# circuit.net
KiCad netlist of a schematic drawn in EAGLE
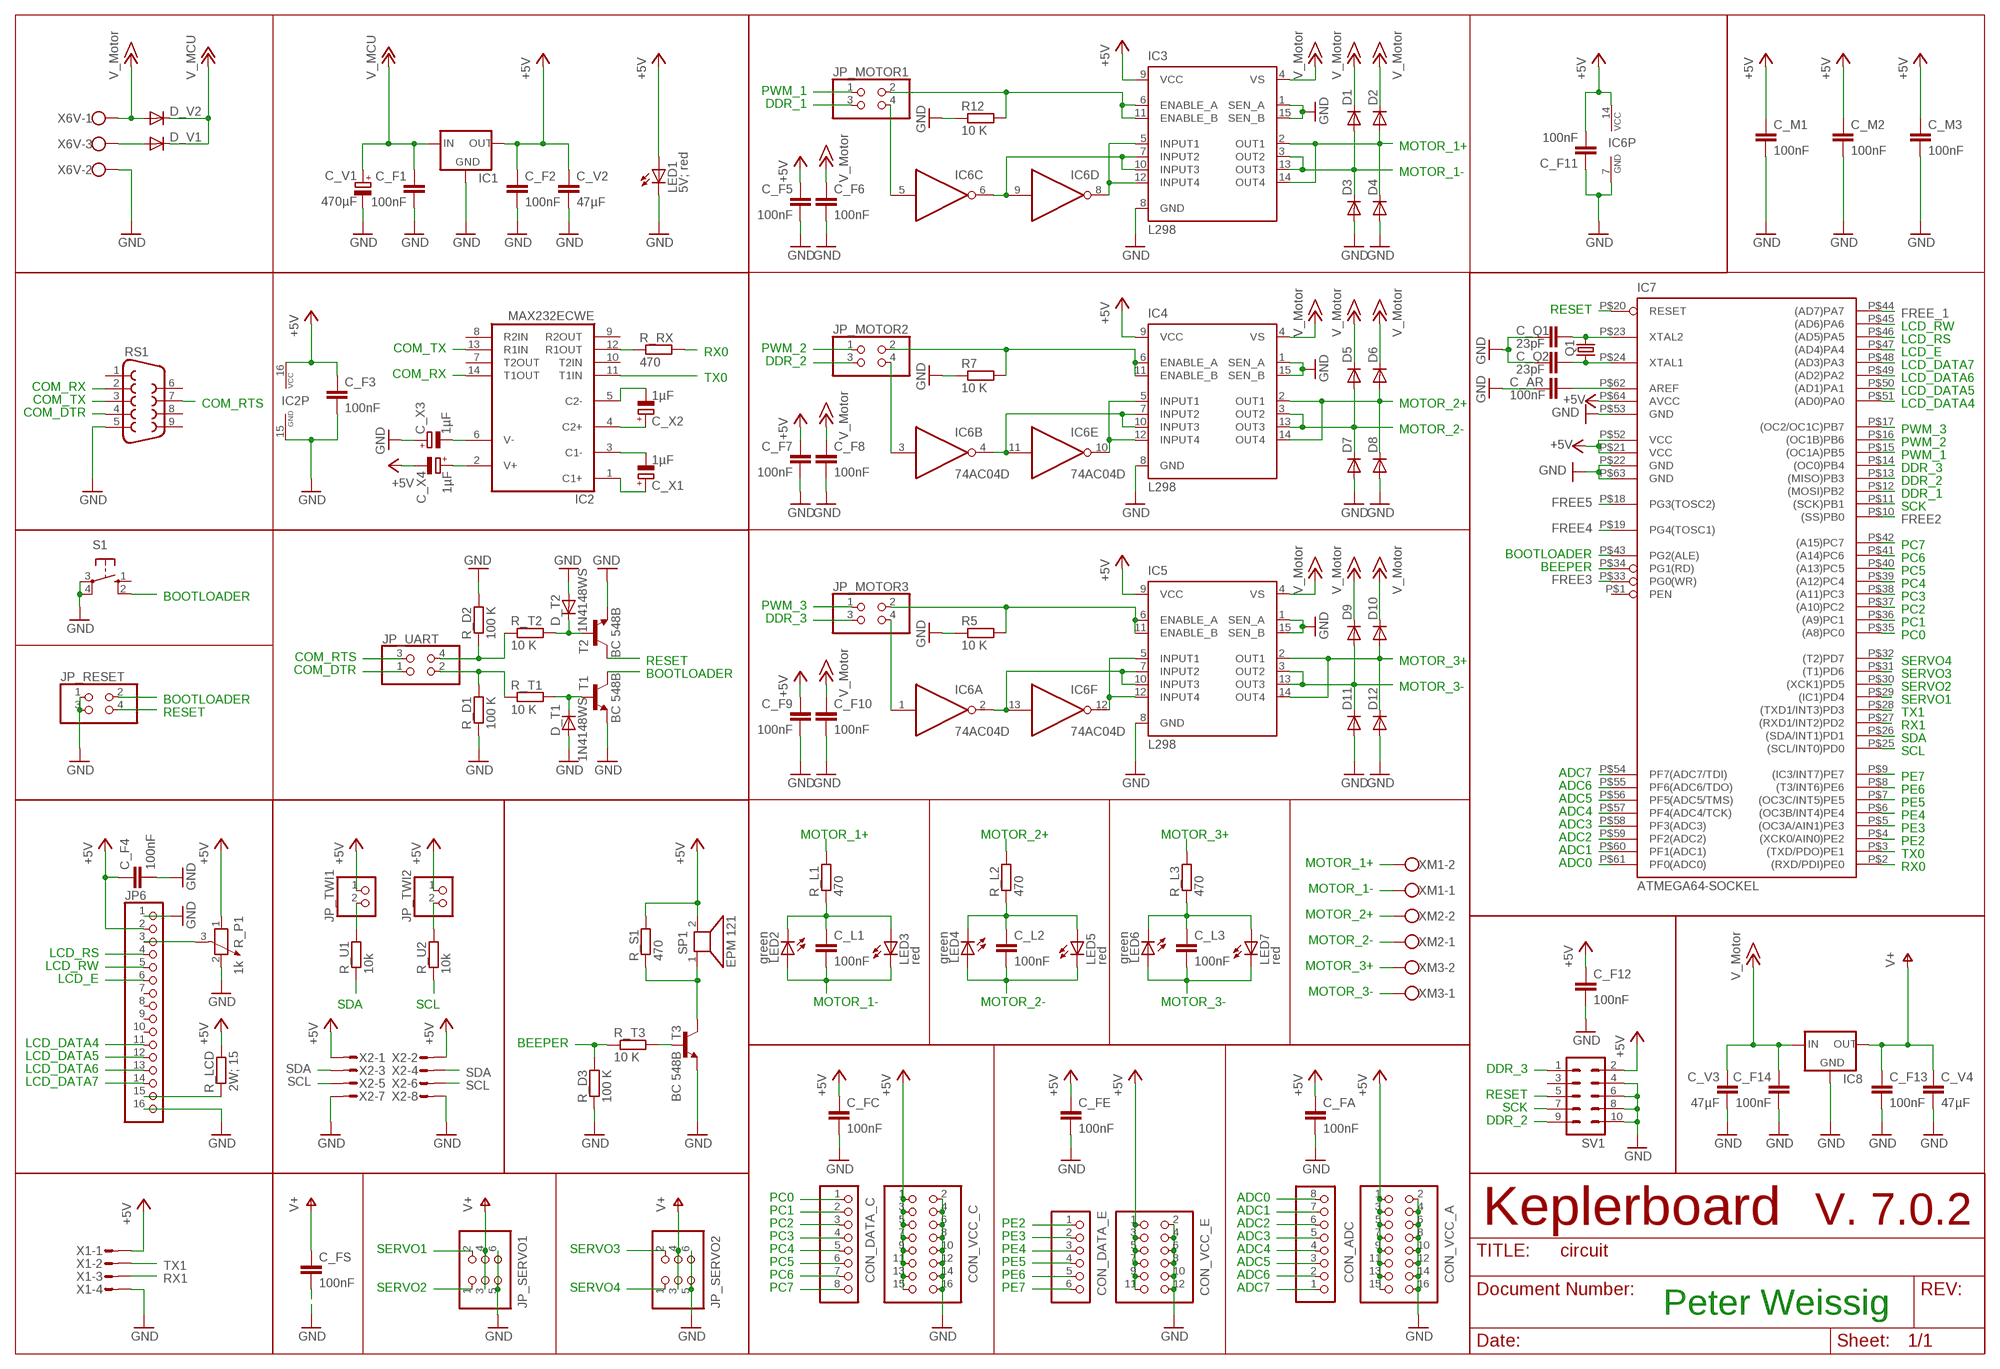
[diagram p0: schematic, sheet 1]

(export (version "E")
  (design (tool "Eeschema 10.0.6"))
  (components
    (comp (ref "CON_ADC")
      (value "PINHD-1X8")
      (footprint "eagle-import:1X08")
      (libsource (lib "eagle-import") (part "PINHD-1X8"))
    )
    (comp (ref "CON_DATA_C")
      (value "PINHD-1X8")
      (footprint "eagle-import:1X08")
      (libsource (lib "eagle-import") (part "PINHD-1X8"))
    )
    (comp (ref "CON_DATA_E")
      (value "PINHD-1X6")
      (footprint "eagle-import:1X06")
      (libsource (lib "eagle-import") (part "PINHD-1X6"))
    )
    (comp (ref "CON_VCC_A")
      (value "PINHD-2X8")
      (footprint "eagle-import:2X08")
      (libsource (lib "eagle-import") (part "PINHD-2X8"))
    )
    (comp (ref "CON_VCC_C")
      (value "PINHD-2X8")
      (footprint "eagle-import:2X08")
      (libsource (lib "eagle-import") (part "PINHD-2X8"))
    )
    (comp (ref "CON_VCC_E")
      (value "PINHD-2X6")
      (footprint "eagle-import:2X06")
      (libsource (lib "eagle-import") (part "PINHD-2X6"))
    )
    (comp (ref "C_AR")
      (value "100nF")
      (footprint "eagle-import:C025-025X050")
      (libsource (lib "eagle-import") (part "C-EU025-025X050"))
    )
    (comp (ref "C_F1")
      (value "100nF")
      (footprint "eagle-import:C1206K")
      (libsource (lib "eagle-import") (part "C-EUC1206K"))
    )
    (comp (ref "C_F2")
      (value "100nF")
      (footprint "eagle-import:C1206K")
      (libsource (lib "eagle-import") (part "C-EUC1206K"))
    )
    (comp (ref "C_F3")
      (value "100nF")
      (footprint "eagle-import:C1206K")
      (libsource (lib "eagle-import") (part "C-EUC1206K"))
    )
    (comp (ref "C_F4")
      (value "100nF")
      (footprint "eagle-import:C025-025X050")
      (libsource (lib "eagle-import") (part "C-EU025-025X050"))
    )
    (comp (ref "C_F5")
      (value "100nF")
      (footprint "eagle-import:C1206K")
      (libsource (lib "eagle-import") (part "C-EUC1206K"))
    )
    (comp (ref "C_F6")
      (value "100nF")
      (footprint "eagle-import:C1206K")
      (libsource (lib "eagle-import") (part "C-EUC1206K"))
    )
    (comp (ref "C_F7")
      (value "100nF")
      (footprint "eagle-import:C1206K")
      (libsource (lib "eagle-import") (part "C-EUC1206K"))
    )
    (comp (ref "C_F8")
      (value "100nF")
      (footprint "eagle-import:C1206K")
      (libsource (lib "eagle-import") (part "C-EUC1206K"))
    )
    (comp (ref "C_F9")
      (value "100nF")
      (footprint "eagle-import:C1206K")
      (libsource (lib "eagle-import") (part "C-EUC1206K"))
    )
    (comp (ref "C_F10")
      (value "100nF")
      (footprint "eagle-import:C1206K")
      (libsource (lib "eagle-import") (part "C-EUC1206K"))
    )
    (comp (ref "C_F11")
      (value "100nF")
      (footprint "eagle-import:C1206K")
      (libsource (lib "eagle-import") (part "C-EUC1206K"))
    )
    (comp (ref "C_F12")
      (value "100nF")
      (footprint "eagle-import:C1206K")
      (libsource (lib "eagle-import") (part "C-EUC1206K"))
    )
    (comp (ref "C_F13")
      (value "100nF")
      (footprint "eagle-import:C1206K")
      (libsource (lib "eagle-import") (part "C-EUC1206K"))
    )
    (comp (ref "C_F14")
      (value "100nF")
      (footprint "eagle-import:C1206K")
      (libsource (lib "eagle-import") (part "C-EUC1206K"))
    )
    (comp (ref "C_FA")
      (value "100nF")
      (footprint "eagle-import:C025-025X050")
      (libsource (lib "eagle-import") (part "C-EU025-025X050"))
    )
    (comp (ref "C_FC")
      (value "100nF")
      (footprint "eagle-import:C025-025X050")
      (libsource (lib "eagle-import") (part "C-EU025-025X050"))
    )
    (comp (ref "C_FE")
      (value "100nF")
      (footprint "eagle-import:C025-025X050")
      (libsource (lib "eagle-import") (part "C-EU025-025X050"))
    )
    (comp (ref "C_FS")
      (value "100nF")
      (footprint "eagle-import:C1206K")
      (libsource (lib "eagle-import") (part "C-EUC1206K"))
    )
    (comp (ref "C_L1")
      (value "100nF")
      (footprint "eagle-import:C1206K")
      (libsource (lib "eagle-import") (part "C-EUC1206K"))
    )
    (comp (ref "C_L2")
      (value "100nF")
      (footprint "eagle-import:C1206K")
      (libsource (lib "eagle-import") (part "C-EUC1206K"))
    )
    (comp (ref "C_L3")
      (value "100nF")
      (footprint "eagle-import:C1206K")
      (libsource (lib "eagle-import") (part "C-EUC1206K"))
    )
    (comp (ref "C_M1")
      (value "100nF")
      (footprint "eagle-import:C025-025X050")
      (libsource (lib "eagle-import") (part "C-EU025-025X050"))
    )
    (comp (ref "C_M2")
      (value "100nF")
      (footprint "eagle-import:C025-025X050")
      (libsource (lib "eagle-import") (part "C-EU025-025X050"))
    )
    (comp (ref "C_M3")
      (value "100nF")
      (footprint "eagle-import:C025-025X050")
      (libsource (lib "eagle-import") (part "C-EU025-025X050"))
    )
    (comp (ref "C_Q1")
      (value "23pF")
      (footprint "eagle-import:C3216")
      (libsource (lib "eagle-import") (part "C-EUC3216"))
    )
    (comp (ref "C_Q2")
      (value "23pF")
      (footprint "eagle-import:C3216")
      (libsource (lib "eagle-import") (part "C-EUC3216"))
    )
    (comp (ref "C_V1")
      (value "470µF")
      (footprint "eagle-import:E5-10,5")
      (libsource (lib "eagle-import") (part "CPOL-EUE5-10.5"))
    )
    (comp (ref "C_V2")
      (value "47µF")
      (footprint "eagle-import:C1210K")
      (libsource (lib "eagle-import") (part "C-EUC1210K"))
    )
    (comp (ref "C_V3")
      (value "47µF")
      (footprint "eagle-import:C1210K")
      (libsource (lib "eagle-import") (part "C-EUC1210K"))
    )
    (comp (ref "C_V4")
      (value "47µF")
      (footprint "eagle-import:C1210K")
      (libsource (lib "eagle-import") (part "C-EUC1210K"))
    )
    (comp (ref "C_X1")
      (value "1µF")
      (footprint "eagle-import:A_3216-18W")
      (libsource (lib "eagle-import") (part "CPOL-EUA/3216-18W"))
    )
    (comp (ref "C_X2")
      (value "1µF")
      (footprint "eagle-import:A_3216-18W")
      (libsource (lib "eagle-import") (part "CPOL-EUA/3216-18W"))
    )
    (comp (ref "C_X3")
      (value "1µF")
      (footprint "eagle-import:A_3216-18W")
      (libsource (lib "eagle-import") (part "CPOL-EUA/3216-18W"))
    )
    (comp (ref "C_X4")
      (value "1µF")
      (footprint "eagle-import:A_3216-18W")
      (libsource (lib "eagle-import") (part "CPOL-EUA/3216-18W"))
    )
    (comp (ref "D1")
      (value "DIODE-SMC")
      (footprint "eagle-import:SMC")
      (libsource (lib "eagle-import") (part "DIODE-SMC"))
    )
    (comp (ref "D2")
      (value "DIODE-SMC")
      (footprint "eagle-import:SMC")
      (libsource (lib "eagle-import") (part "DIODE-SMC"))
    )
    (comp (ref "D3")
      (value "DIODE-SMC")
      (footprint "eagle-import:SMC")
      (libsource (lib "eagle-import") (part "DIODE-SMC"))
    )
    (comp (ref "D4")
      (value "DIODE-SMC")
      (footprint "eagle-import:SMC")
      (libsource (lib "eagle-import") (part "DIODE-SMC"))
    )
    (comp (ref "D5")
      (value "DIODE-SMC")
      (footprint "eagle-import:SMC")
      (libsource (lib "eagle-import") (part "DIODE-SMC"))
    )
    (comp (ref "D6")
      (value "DIODE-SMC")
      (footprint "eagle-import:SMC")
      (libsource (lib "eagle-import") (part "DIODE-SMC"))
    )
    (comp (ref "D7")
      (value "DIODE-SMC")
      (footprint "eagle-import:SMC")
      (libsource (lib "eagle-import") (part "DIODE-SMC"))
    )
    (comp (ref "D8")
      (value "DIODE-SMC")
      (footprint "eagle-import:SMC")
      (libsource (lib "eagle-import") (part "DIODE-SMC"))
    )
    (comp (ref "D9")
      (value "DIODE-SMC")
      (footprint "eagle-import:SMC")
      (libsource (lib "eagle-import") (part "DIODE-SMC"))
    )
    (comp (ref "D10")
      (value "DIODE-SMC")
      (footprint "eagle-import:SMC")
      (libsource (lib "eagle-import") (part "DIODE-SMC"))
    )
    (comp (ref "D11")
      (value "DIODE-SMC")
      (footprint "eagle-import:SMC")
      (libsource (lib "eagle-import") (part "DIODE-SMC"))
    )
    (comp (ref "D12")
      (value "DIODE-SMC")
      (footprint "eagle-import:SMC")
      (libsource (lib "eagle-import") (part "DIODE-SMC"))
    )
    (comp (ref "D_T1")
      (value "1N4148WS")
      (footprint "eagle-import:SOD323-W")
      (libsource (lib "eagle-import") (part "DIODE-SOD323-W"))
    )
    (comp (ref "D_T2")
      (value "1N4148WS")
      (footprint "eagle-import:SOD323-W")
      (libsource (lib "eagle-import") (part "DIODE-SOD323-W"))
    )
    (comp (ref "D_V1")
      (value "DIODE-SMC")
      (footprint "eagle-import:SMC")
      (libsource (lib "eagle-import") (part "DIODE-SMC"))
    )
    (comp (ref "D_V2")
      (value "DIODE-SMC")
      (footprint "eagle-import:SMC")
      (libsource (lib "eagle-import") (part "DIODE-SMC"))
    )
    (comp (ref "IC1")
      (value "78XXS")
      (footprint "eagle-import:78XXS")
      (libsource (lib "eagle-import") (part "78XXS"))
    )
    (comp (ref "IC2")
      (value "MAX232ECWE")
      (footprint "eagle-import:SO16L")
      (libsource (lib "eagle-import") (part "MAX232ECWE"))
    )
    (comp (ref "IC3")
      (value "L298")
      (footprint "eagle-import:MULTIWATT-15")
      (fields (field (name "MPN") "L298N"))
      (libsource (lib "eagle-import") (part "L298"))
    )
    (comp (ref "IC4")
      (value "L298")
      (footprint "eagle-import:MULTIWATT-15")
      (fields (field (name "MPN") "L298N"))
      (libsource (lib "eagle-import") (part "L298"))
    )
    (comp (ref "IC5")
      (value "L298")
      (footprint "eagle-import:MULTIWATT-15")
      (fields (field (name "MPN") "L298N"))
      (libsource (lib "eagle-import") (part "L298"))
    )
    (comp (ref "IC6")
      (value "74AC04D")
      (footprint "eagle-import:SO14")
      (libsource (lib "eagle-import") (part "7404DAC"))
    )
    (comp (ref "IC7")
      (value "ATMEGA64-SOCKEL")
      (footprint "eagle-import:SOCKEL_TQFP64")
      (libsource (lib "eagle-import") (part "ATMEGA64-SOCKEL"))
    )
    (comp (ref "IC8")
      (value "78XXS")
      (footprint "eagle-import:78XXS")
      (libsource (lib "eagle-import") (part "78XXS"))
    )
    (comp (ref "JP6")
      (value "PINHD-1X16")
      (footprint "eagle-import:1X16")
      (libsource (lib "eagle-import") (part "PINHD-1X16"))
    )
    (comp (ref "JP_MOTOR1")
      (value "PINHD-2X2")
      (footprint "eagle-import:2X02")
      (libsource (lib "eagle-import") (part "PINHD-2X2"))
    )
    (comp (ref "JP_MOTOR2")
      (value "PINHD-2X2")
      (footprint "eagle-import:2X02")
      (libsource (lib "eagle-import") (part "PINHD-2X2"))
    )
    (comp (ref "JP_MOTOR3")
      (value "PINHD-2X2")
      (footprint "eagle-import:2X02")
      (libsource (lib "eagle-import") (part "PINHD-2X2"))
    )
    (comp (ref "JP_RESET")
      (value "PINHD-2X2")
      (footprint "eagle-import:2X02")
      (libsource (lib "eagle-import") (part "PINHD-2X2"))
    )
    (comp (ref "JP_SERVO1")
      (value "PINHD-2X3")
      (footprint "eagle-import:2X03")
      (libsource (lib "eagle-import") (part "PINHD-2X3"))
    )
    (comp (ref "JP_SERVO2")
      (value "PINHD-2X3")
      (footprint "eagle-import:2X03")
      (libsource (lib "eagle-import") (part "PINHD-2X3"))
    )
    (comp (ref "JP_TWI1")
      (value "PINHD-1X2")
      (footprint "eagle-import:1X02")
      (libsource (lib "eagle-import") (part "PINHD-1X2"))
    )
    (comp (ref "JP_TWI2")
      (value "PINHD-1X2")
      (footprint "eagle-import:1X02")
      (libsource (lib "eagle-import") (part "PINHD-1X2"))
    )
    (comp (ref "JP_UART")
      (value "PINHD-2X2")
      (footprint "eagle-import:2X02")
      (libsource (lib "eagle-import") (part "PINHD-2X2"))
    )
    (comp (ref "LED1")
      (value "5V; red")
      (footprint "eagle-import:LED3MM")
      (libsource (lib "eagle-import") (part "LED3MM"))
    )
    (comp (ref "LED2")
      (value "green")
      (footprint "eagle-import:CHIPLED_1206")
      (libsource (lib "eagle-import") (part "LEDCHIPLED_1206"))
    )
    (comp (ref "LED3")
      (value "red")
      (footprint "eagle-import:CHIPLED_1206")
      (libsource (lib "eagle-import") (part "LEDCHIPLED_1206"))
    )
    (comp (ref "LED4")
      (value "green")
      (footprint "eagle-import:CHIPLED_1206")
      (libsource (lib "eagle-import") (part "LEDCHIPLED_1206"))
    )
    (comp (ref "LED5")
      (value "red")
      (footprint "eagle-import:CHIPLED_1206")
      (libsource (lib "eagle-import") (part "LEDCHIPLED_1206"))
    )
    (comp (ref "LED6")
      (value "green")
      (footprint "eagle-import:CHIPLED_1206")
      (libsource (lib "eagle-import") (part "LEDCHIPLED_1206"))
    )
    (comp (ref "LED7")
      (value "red")
      (footprint "eagle-import:CHIPLED_1206")
      (libsource (lib "eagle-import") (part "LEDCHIPLED_1206"))
    )
    (comp (ref "Q1")
      (value "CRYSTALHC49UP")
      (footprint "eagle-import:HC49UP")
      (libsource (lib "eagle-import") (part "CRYSTALHC49UP"))
    )
    (comp (ref "R5")
      (value "10 K")
      (footprint "eagle-import:R1206")
      (libsource (lib "eagle-import") (part "R-EU_R1206"))
    )
    (comp (ref "R7")
      (value "10 K")
      (footprint "eagle-import:R1206")
      (libsource (lib "eagle-import") (part "R-EU_R1206"))
    )
    (comp (ref "R12")
      (value "10 K")
      (footprint "eagle-import:R1206")
      (libsource (lib "eagle-import") (part "R-EU_R1206"))
    )
    (comp (ref "RS1")
      (value "F09H")
      (footprint "eagle-import:F09H")
      (libsource (lib "eagle-import") (part "F09H"))
    )
    (comp (ref "R_D1")
      (value "100 K")
      (footprint "eagle-import:R1206")
      (libsource (lib "eagle-import") (part "R-EU_R1206"))
    )
    (comp (ref "R_D2")
      (value "100 K")
      (footprint "eagle-import:R1206")
      (libsource (lib "eagle-import") (part "R-EU_R1206"))
    )
    (comp (ref "R_D3")
      (value "100 K")
      (footprint "eagle-import:R1206")
      (libsource (lib "eagle-import") (part "R-EU_R1206"))
    )
    (comp (ref "R_L1")
      (value "470")
      (footprint "eagle-import:R1206")
      (libsource (lib "eagle-import") (part "R-EU_R1206"))
    )
    (comp (ref "R_L2")
      (value "470")
      (footprint "eagle-import:R1206")
      (libsource (lib "eagle-import") (part "R-EU_R1206"))
    )
    (comp (ref "R_L3")
      (value "470")
      (footprint "eagle-import:R1206")
      (libsource (lib "eagle-import") (part "R-EU_R1206"))
    )
    (comp (ref "R_LCD")
      (value "2W; 15")
      (footprint "eagle-import:0414_15")
      (libsource (lib "eagle-import") (part "R-EU_0414/15"))
    )
    (comp (ref "R_P1")
      (value "1k")
      (footprint "eagle-import:PT-10")
      (libsource (lib "eagle-import") (part "POTENTIOMETER_PT-10"))
    )
    (comp (ref "R_RX")
      (value "470")
      (footprint "eagle-import:R1206")
      (libsource (lib "eagle-import") (part "R-EU_R1206"))
    )
    (comp (ref "R_S1")
      (value "470")
      (footprint "eagle-import:R1206")
      (libsource (lib "eagle-import") (part "R-EU_R1206"))
    )
    (comp (ref "R_T1")
      (value "10 K")
      (footprint "eagle-import:R1206")
      (libsource (lib "eagle-import") (part "R-EU_R1206"))
    )
    (comp (ref "R_T2")
      (value "10 K")
      (footprint "eagle-import:R1206")
      (libsource (lib "eagle-import") (part "R-EU_R1206"))
    )
    (comp (ref "R_T3")
      (value "10 K")
      (footprint "eagle-import:R1206")
      (libsource (lib "eagle-import") (part "R-EU_R1206"))
    )
    (comp (ref "R_U1")
      (value "10k")
      (footprint "eagle-import:R1206")
      (libsource (lib "eagle-import") (part "R-EU_R1206"))
    )
    (comp (ref "R_U2")
      (value "10k")
      (footprint "eagle-import:R1206")
      (libsource (lib "eagle-import") (part "R-EU_R1206"))
    )
    (comp (ref "S1")
      (value "TASTER")
      (footprint "eagle-import:TASTER_SMD")
      (libsource (lib "eagle-import") (part "TASTER"))
    )
    (comp (ref "SP1")
      (value "EPM 121")
      (footprint "eagle-import:AL60P")
      (libsource (lib "eagle-import") (part "AL60P"))
    )
    (comp (ref "SV1")
      (value "ML10")
      (footprint "eagle-import:ML10")
      (libsource (lib "eagle-import") (part "ML10"))
    )
    (comp (ref "T1")
      (value "BC 548B")
      (footprint "eagle-import:TO92")
      (libsource (lib "eagle-import") (part "2N3565"))
    )
    (comp (ref "T2")
      (value "BC 548B")
      (footprint "eagle-import:TO92")
      (libsource (lib "eagle-import") (part "2N3565"))
    )
    (comp (ref "T3")
      (value "BC 548B")
      (footprint "eagle-import:TO92")
      (libsource (lib "eagle-import") (part "2N3565"))
    )
    (comp (ref "X1")
      (value "MICROMATCH-4")
      (footprint "eagle-import:MICROMATCH-4")
      (fields (field (name "MPN") "7-215464-4"))
      (libsource (lib "eagle-import") (part "MICROMATCH-4"))
    )
    (comp (ref "X2")
      (value "MICROMATCH-8")
      (footprint "eagle-import:MICROMATCH-8")
      (fields (field (name "MF") "FARNELL") (field (name "MPN") "7-215464-8"))
      (libsource (lib "eagle-import") (part "MICROMATCH-8"))
    )
    (comp (ref "X6V")
      (value "W237-103")
      (footprint "eagle-import:W237-103")
      (libsource (lib "eagle-import") (part "W237-103"))
    )
    (comp (ref "XM1")
      (value "W237-102")
      (footprint "eagle-import:W237-102")
      (libsource (lib "eagle-import") (part "W237-102"))
    )
    (comp (ref "XM2")
      (value "W237-102")
      (footprint "eagle-import:W237-102")
      (libsource (lib "eagle-import") (part "W237-102"))
    )
    (comp (ref "XM3")
      (value "W237-102")
      (footprint "eagle-import:W237-102")
      (libsource (lib "eagle-import") (part "W237-102"))
    )
  )
  (nets
    (net (code "1") (name "+5V") (class "Default")
      (node (ref "CON_VCC_A") (pin "1") (pinfunction "1_1") (pintype "passive"))
      (node (ref "CON_VCC_A") (pin "11") (pinfunction "11_11") (pintype "passive"))
      (node (ref "CON_VCC_A") (pin "13") (pinfunction "13_13") (pintype "passive"))
      (node (ref "CON_VCC_A") (pin "15") (pinfunction "15_15") (pintype "passive"))
      (node (ref "CON_VCC_A") (pin "3") (pinfunction "3_3") (pintype "passive"))
      (node (ref "CON_VCC_A") (pin "5") (pinfunction "5_5") (pintype "passive"))
      (node (ref "CON_VCC_A") (pin "7") (pinfunction "7_7") (pintype "passive"))
      (node (ref "CON_VCC_A") (pin "9") (pinfunction "9_9") (pintype "passive"))
      (node (ref "CON_VCC_C") (pin "1") (pinfunction "1_1") (pintype "passive"))
      (node (ref "CON_VCC_C") (pin "11") (pinfunction "11_11") (pintype "passive"))
      (node (ref "CON_VCC_C") (pin "13") (pinfunction "13_13") (pintype "passive"))
      (node (ref "CON_VCC_C") (pin "15") (pinfunction "15_15") (pintype "passive"))
      (node (ref "CON_VCC_C") (pin "3") (pinfunction "3_3") (pintype "passive"))
      (node (ref "CON_VCC_C") (pin "5") (pinfunction "5_5") (pintype "passive"))
      (node (ref "CON_VCC_C") (pin "7") (pinfunction "7_7") (pintype "passive"))
      (node (ref "CON_VCC_C") (pin "9") (pinfunction "9_9") (pintype "passive"))
      (node (ref "CON_VCC_E") (pin "1") (pinfunction "1_1") (pintype "passive"))
      (node (ref "CON_VCC_E") (pin "11") (pinfunction "11_11") (pintype "passive"))
      (node (ref "CON_VCC_E") (pin "3") (pinfunction "3_3") (pintype "passive"))
      (node (ref "CON_VCC_E") (pin "5") (pinfunction "5_5") (pintype "passive"))
      (node (ref "CON_VCC_E") (pin "7") (pinfunction "7_7") (pintype "passive"))
      (node (ref "CON_VCC_E") (pin "9") (pinfunction "9_9") (pintype "passive"))
      (node (ref "C_F11") (pin "2") (pinfunction "2_2") (pintype "passive"))
      (node (ref "C_F12") (pin "1") (pinfunction "1_1") (pintype "passive"))
      (node (ref "C_F2") (pin "1") (pinfunction "1_1") (pintype "passive"))
      (node (ref "C_F3") (pin "1") (pinfunction "1_1") (pintype "passive"))
      (node (ref "C_F4") (pin "1") (pinfunction "1_1") (pintype "passive"))
      (node (ref "C_F5") (pin "1") (pinfunction "1_1") (pintype "passive"))
      (node (ref "C_F7") (pin "1") (pinfunction "1_1") (pintype "passive"))
      (node (ref "C_F9") (pin "1") (pinfunction "1_1") (pintype "passive"))
      (node (ref "C_FA") (pin "1") (pinfunction "1_1") (pintype "passive"))
      (node (ref "C_FC") (pin "1") (pinfunction "1_1") (pintype "passive"))
      (node (ref "C_FE") (pin "1") (pinfunction "1_1") (pintype "passive"))
      (node (ref "C_M1") (pin "1") (pinfunction "1_1") (pintype "passive"))
      (node (ref "C_M2") (pin "1") (pinfunction "1_1") (pintype "passive"))
      (node (ref "C_M3") (pin "1") (pinfunction "1_1") (pintype "passive"))
      (node (ref "C_V2") (pin "1") (pinfunction "1_1") (pintype "passive"))
      (node (ref "C_X4") (pin "-") (pinfunction "-_-") (pintype "passive"))
      (node (ref "IC1") (pin "OUT") (pinfunction "OUT_OUT") (pintype "passive"))
      (node (ref "IC2") (pin "16") (pinfunction "VCC_16") (pintype "power_in"))
      (node (ref "IC3") (pin "9") (pinfunction "VCC_9") (pintype "power_in"))
      (node (ref "IC4") (pin "9") (pinfunction "VCC_9") (pintype "power_in"))
      (node (ref "IC5") (pin "9") (pinfunction "VCC_9") (pintype "power_in"))
      (node (ref "IC6") (pin "14") (pinfunction "VCC_14") (pintype "power_in"))
      (node (ref "IC7") (pin "P$21") (pinfunction "VCC_P$21") (pintype "power_in"))
      (node (ref "IC7") (pin "P$52") (pinfunction "VCC_P$52") (pintype "power_in"))
      (node (ref "IC7") (pin "P$64") (pinfunction "AVCC_P$64") (pintype "power_in"))
      (node (ref "JP6") (pin "2") (pinfunction "2_2") (pintype "passive"))
      (node (ref "JP_TWI1") (pin "1") (pinfunction "1_1") (pintype "passive"))
      (node (ref "JP_TWI2") (pin "1") (pinfunction "1_1") (pintype "passive"))
      (node (ref "LED1") (pin "A") (pinfunction "A_A") (pintype "passive"))
      (node (ref "R_LCD") (pin "1") (pinfunction "1_1") (pintype "passive"))
      (node (ref "R_P1") (pin "1") (pinfunction "1_1") (pintype "passive"))
      (node (ref "R_S1") (pin "2") (pinfunction "2_2") (pintype "passive"))
      (node (ref "SP1") (pin "2") (pinfunction "2_2") (pintype "passive"))
      (node (ref "SV1") (pin "2") (pinfunction "2_2") (pintype "passive"))
      (node (ref "X1") (pin "1") (pinfunction "S_1") (pintype "passive"))
      (node (ref "X2") (pin "1") (pinfunction "S_1") (pintype "passive"))
      (node (ref "X2") (pin "2") (pinfunction "S_2") (pintype "passive"))
    )
    (net (code "2") (name "/ADC0") (class "Default")
      (node (ref "CON_ADC") (pin "8") (pinfunction "8_8") (pintype "passive"))
      (node (ref "IC7") (pin "P$61") (pinfunction "PF0(ADC0)_P$61") (pintype "input"))
    )
    (net (code "3") (name "/ADC1") (class "Default")
      (node (ref "CON_ADC") (pin "7") (pinfunction "7_7") (pintype "passive"))
      (node (ref "IC7") (pin "P$60") (pinfunction "PF1(ADC1)_P$60") (pintype "input"))
    )
    (net (code "4") (name "/ADC2") (class "Default")
      (node (ref "CON_ADC") (pin "6") (pinfunction "6_6") (pintype "passive"))
      (node (ref "IC7") (pin "P$59") (pinfunction "PF2(ADC2)_P$59") (pintype "input"))
    )
    (net (code "5") (name "/ADC3") (class "Default")
      (node (ref "CON_ADC") (pin "5") (pinfunction "5_5") (pintype "passive"))
      (node (ref "IC7") (pin "P$58") (pinfunction "PF3(ADC3)_P$58") (pintype "input"))
    )
    (net (code "6") (name "/ADC4") (class "Default")
      (node (ref "CON_ADC") (pin "4") (pinfunction "4_4") (pintype "passive"))
      (node (ref "IC7") (pin "P$57") (pinfunction "PF4(ADC4/TCK)_P$57") (pintype "input"))
    )
    (net (code "7") (name "/ADC5") (class "Default")
      (node (ref "CON_ADC") (pin "3") (pinfunction "3_3") (pintype "passive"))
      (node (ref "IC7") (pin "P$56") (pinfunction "PF5(ADC5/TMS)_P$56") (pintype "input"))
    )
    (net (code "8") (name "/ADC6") (class "Default")
      (node (ref "CON_ADC") (pin "2") (pinfunction "2_2") (pintype "passive"))
      (node (ref "IC7") (pin "P$55") (pinfunction "PF6(ADC6/TDO)_P$55") (pintype "input"))
    )
    (net (code "9") (name "/ADC7") (class "Default")
      (node (ref "CON_ADC") (pin "1") (pinfunction "1_1") (pintype "passive"))
      (node (ref "IC7") (pin "P$54") (pinfunction "PF7(ADC7/TDI)_P$54") (pintype "input"))
    )
    (net (code "10") (name "/BEEPER") (class "Default")
      (node (ref "IC7") (pin "P$34") (pinfunction "PG1(RD)_P$34") (pintype "bidirectional"))
      (node (ref "R_D3") (pin "2") (pinfunction "2_2") (pintype "passive"))
      (node (ref "R_T3") (pin "1") (pinfunction "1_1") (pintype "passive"))
    )
    (net (code "11") (name "/BOOTLOADER") (class "Default")
      (node (ref "IC7") (pin "P$43") (pinfunction "PG2(ALE)_P$43") (pintype "bidirectional"))
      (node (ref "JP_RESET") (pin "2") (pinfunction "2_2") (pintype "passive"))
      (node (ref "S1") (pin "2") (pinfunction "S1_2") (pintype "passive"))
      (node (ref "T1") (pin "1") (pinfunction "C_1") (pintype "passive"))
    )
    (net (code "12") (name "/COM_DTR") (class "Default")
      (node (ref "JP_UART") (pin "1") (pinfunction "1_1") (pintype "passive"))
      (node (ref "RS1") (pin "4") (pinfunction "4_4") (pintype "passive"))
    )
    (net (code "13") (name "/COM_RTS") (class "Default")
      (node (ref "JP_UART") (pin "3") (pinfunction "3_3") (pintype "passive"))
      (node (ref "RS1") (pin "7") (pinfunction "7_7") (pintype "passive"))
    )
    (net (code "14") (name "/COM_RX") (class "Default")
      (node (ref "IC2") (pin "14") (pinfunction "T1OUT_14") (pintype "output"))
      (node (ref "RS1") (pin "2") (pinfunction "2_2") (pintype "passive"))
    )
    (net (code "15") (name "/COM_TX") (class "Default")
      (node (ref "IC2") (pin "13") (pinfunction "R1IN_13") (pintype "input"))
      (node (ref "RS1") (pin "3") (pinfunction "3_3") (pintype "passive"))
    )
    (net (code "16") (name "/DDR_1") (class "Default")
      (node (ref "IC7") (pin "P$12") (pinfunction "(MOSI)PB2_P$12") (pintype "bidirectional"))
      (node (ref "JP_MOTOR1") (pin "3") (pinfunction "3_3") (pintype "passive"))
    )
    (net (code "17") (name "/DDR_2") (class "Default")
      (node (ref "IC7") (pin "P$13") (pinfunction "(MISO)PB3_P$13") (pintype "bidirectional"))
      (node (ref "JP_MOTOR2") (pin "3") (pinfunction "3_3") (pintype "passive"))
      (node (ref "SV1") (pin "9") (pinfunction "9_9") (pintype "passive"))
    )
    (net (code "18") (name "/DDR_3") (class "Default")
      (node (ref "IC7") (pin "P$14") (pinfunction "(OC0)PB4_P$14") (pintype "bidirectional"))
      (node (ref "JP_MOTOR3") (pin "3") (pinfunction "3_3") (pintype "passive"))
      (node (ref "SV1") (pin "1") (pinfunction "1_1") (pintype "passive"))
    )
    (net (code "19") (name "/FREE2") (class "Default")
      (node (ref "IC7") (pin "P$10") (pinfunction "(SS)PB0_P$10") (pintype "bidirectional"))
    )
    (net (code "20") (name "/FREE3") (class "Default")
      (node (ref "IC7") (pin "P$33") (pinfunction "PG0(WR)_P$33") (pintype "bidirectional"))
    )
    (net (code "21") (name "/FREE4") (class "Default")
      (node (ref "IC7") (pin "P$19") (pinfunction "PG4(TOSC1)_P$19") (pintype "bidirectional"))
    )
    (net (code "22") (name "/FREE5") (class "Default")
      (node (ref "IC7") (pin "P$18") (pinfunction "PG3(TOSC2)_P$18") (pintype "bidirectional"))
    )
    (net (code "23") (name "/FREE_1") (class "Default")
      (node (ref "IC7") (pin "P$44") (pinfunction "(AD7)PA7_P$44") (pintype "bidirectional"))
    )
    (net (code "24") (name "/LCD_DATA4") (class "Default")
      (node (ref "IC7") (pin "P$51") (pinfunction "(AD0)PA0_P$51") (pintype "bidirectional"))
      (node (ref "JP6") (pin "11") (pinfunction "11_11") (pintype "passive"))
    )
    (net (code "25") (name "/LCD_DATA5") (class "Default")
      (node (ref "IC7") (pin "P$50") (pinfunction "(AD1)PA1_P$50") (pintype "bidirectional"))
      (node (ref "JP6") (pin "12") (pinfunction "12_12") (pintype "passive"))
    )
    (net (code "26") (name "/LCD_DATA6") (class "Default")
      (node (ref "IC7") (pin "P$49") (pinfunction "(AD2)PA2_P$49") (pintype "bidirectional"))
      (node (ref "JP6") (pin "13") (pinfunction "13_13") (pintype "passive"))
    )
    (net (code "27") (name "/LCD_DATA7") (class "Default")
      (node (ref "IC7") (pin "P$48") (pinfunction "(AD3)PA3_P$48") (pintype "bidirectional"))
      (node (ref "JP6") (pin "14") (pinfunction "14_14") (pintype "passive"))
    )
    (net (code "28") (name "/LCD_E") (class "Default")
      (node (ref "IC7") (pin "P$47") (pinfunction "(AD4)PA4_P$47") (pintype "bidirectional"))
      (node (ref "JP6") (pin "6") (pinfunction "6_6") (pintype "passive"))
    )
    (net (code "29") (name "/LCD_RS") (class "Default")
      (node (ref "IC7") (pin "P$46") (pinfunction "(AD5)PA5_P$46") (pintype "bidirectional"))
      (node (ref "JP6") (pin "4") (pinfunction "4_4") (pintype "passive"))
    )
    (net (code "30") (name "/LCD_RW") (class "Default")
      (node (ref "IC7") (pin "P$45") (pinfunction "(AD6)PA6_P$45") (pintype "bidirectional"))
      (node (ref "JP6") (pin "5") (pinfunction "5_5") (pintype "passive"))
    )
    (net (code "31") (name "/MOTOR_1+") (class "Default")
      (node (ref "D2") (pin "A") (pinfunction "A_A") (pintype "passive"))
      (node (ref "D4") (pin "C") (pinfunction "C_C") (pintype "passive"))
      (node (ref "IC3") (pin "14") (pinfunction "OUT4_14") (pintype "output"))
      (node (ref "IC3") (pin "2") (pinfunction "OUT1_2") (pintype "output"))
      (node (ref "R_L1") (pin "2") (pinfunction "2_2") (pintype "passive"))
      (node (ref "XM1") (pin "2") (pinfunction "KL_2") (pintype "passive"))
    )
    (net (code "32") (name "/MOTOR_1-") (class "Default")
      (node (ref "C_L1") (pin "2") (pinfunction "2_2") (pintype "passive"))
      (node (ref "D1") (pin "A") (pinfunction "A_A") (pintype "passive"))
      (node (ref "D3") (pin "C") (pinfunction "C_C") (pintype "passive"))
      (node (ref "IC3") (pin "13") (pinfunction "OUT3_13") (pintype "output"))
      (node (ref "IC3") (pin "3") (pinfunction "OUT2_3") (pintype "output"))
      (node (ref "LED2") (pin "A") (pinfunction "A_A") (pintype "passive"))
      (node (ref "LED3") (pin "C") (pinfunction "C_C") (pintype "passive"))
      (node (ref "XM1") (pin "1") (pinfunction "KL_1") (pintype "passive"))
    )
    (net (code "33") (name "/MOTOR_2+") (class "Default")
      (node (ref "D6") (pin "A") (pinfunction "A_A") (pintype "passive"))
      (node (ref "D8") (pin "C") (pinfunction "C_C") (pintype "passive"))
      (node (ref "IC4") (pin "14") (pinfunction "OUT4_14") (pintype "output"))
      (node (ref "IC4") (pin "2") (pinfunction "OUT1_2") (pintype "output"))
      (node (ref "R_L2") (pin "2") (pinfunction "2_2") (pintype "passive"))
      (node (ref "XM2") (pin "2") (pinfunction "KL_2") (pintype "passive"))
    )
    (net (code "34") (name "/MOTOR_2-") (class "Default")
      (node (ref "C_L2") (pin "2") (pinfunction "2_2") (pintype "passive"))
      (node (ref "D5") (pin "A") (pinfunction "A_A") (pintype "passive"))
      (node (ref "D7") (pin "C") (pinfunction "C_C") (pintype "passive"))
      (node (ref "IC4") (pin "13") (pinfunction "OUT3_13") (pintype "output"))
      (node (ref "IC4") (pin "3") (pinfunction "OUT2_3") (pintype "output"))
      (node (ref "LED4") (pin "A") (pinfunction "A_A") (pintype "passive"))
      (node (ref "LED5") (pin "C") (pinfunction "C_C") (pintype "passive"))
      (node (ref "XM2") (pin "1") (pinfunction "KL_1") (pintype "passive"))
    )
    (net (code "35") (name "/MOTOR_3+") (class "Default")
      (node (ref "D10") (pin "A") (pinfunction "A_A") (pintype "passive"))
      (node (ref "D12") (pin "C") (pinfunction "C_C") (pintype "passive"))
      (node (ref "IC5") (pin "14") (pinfunction "OUT4_14") (pintype "output"))
      (node (ref "IC5") (pin "2") (pinfunction "OUT1_2") (pintype "output"))
      (node (ref "R_L3") (pin "2") (pinfunction "2_2") (pintype "passive"))
      (node (ref "XM3") (pin "2") (pinfunction "KL_2") (pintype "passive"))
    )
    (net (code "36") (name "/MOTOR_3-") (class "Default")
      (node (ref "C_L3") (pin "2") (pinfunction "2_2") (pintype "passive"))
      (node (ref "D11") (pin "C") (pinfunction "C_C") (pintype "passive"))
      (node (ref "D9") (pin "A") (pinfunction "A_A") (pintype "passive"))
      (node (ref "IC5") (pin "13") (pinfunction "OUT3_13") (pintype "output"))
      (node (ref "IC5") (pin "3") (pinfunction "OUT2_3") (pintype "output"))
      (node (ref "LED6") (pin "A") (pinfunction "A_A") (pintype "passive"))
      (node (ref "LED7") (pin "C") (pinfunction "C_C") (pintype "passive"))
      (node (ref "XM3") (pin "1") (pinfunction "KL_1") (pintype "passive"))
    )
    (net (code "37") (name "/PC0") (class "Default")
      (node (ref "CON_DATA_C") (pin "1") (pinfunction "1_1") (pintype "passive"))
      (node (ref "IC7") (pin "P$35") (pinfunction "(A8)PC0_P$35") (pintype "output"))
    )
    (net (code "38") (name "/PC1") (class "Default")
      (node (ref "CON_DATA_C") (pin "2") (pinfunction "2_2") (pintype "passive"))
      (node (ref "IC7") (pin "P$36") (pinfunction "(A9)PC1_P$36") (pintype "output"))
    )
    (net (code "39") (name "/PC2") (class "Default")
      (node (ref "CON_DATA_C") (pin "3") (pinfunction "3_3") (pintype "passive"))
      (node (ref "IC7") (pin "P$37") (pinfunction "(A10)PC2_P$37") (pintype "output"))
    )
    (net (code "40") (name "/PC3") (class "Default")
      (node (ref "CON_DATA_C") (pin "4") (pinfunction "4_4") (pintype "passive"))
      (node (ref "IC7") (pin "P$38") (pinfunction "(A11)PC3_P$38") (pintype "output"))
    )
    (net (code "41") (name "/PC4") (class "Default")
      (node (ref "CON_DATA_C") (pin "5") (pinfunction "5_5") (pintype "passive"))
      (node (ref "IC7") (pin "P$39") (pinfunction "(A12)PC4_P$39") (pintype "output"))
    )
    (net (code "42") (name "/PC5") (class "Default")
      (node (ref "CON_DATA_C") (pin "6") (pinfunction "6_6") (pintype "passive"))
      (node (ref "IC7") (pin "P$40") (pinfunction "(A13)PC5_P$40") (pintype "output"))
    )
    (net (code "43") (name "/PC6") (class "Default")
      (node (ref "CON_DATA_C") (pin "7") (pinfunction "7_7") (pintype "passive"))
      (node (ref "IC7") (pin "P$41") (pinfunction "(A14)PC6_P$41") (pintype "output"))
    )
    (net (code "44") (name "/PC7") (class "Default")
      (node (ref "CON_DATA_C") (pin "8") (pinfunction "8_8") (pintype "passive"))
      (node (ref "IC7") (pin "P$42") (pinfunction "(A15)PC7_P$42") (pintype "output"))
    )
    (net (code "45") (name "/PE2") (class "Default")
      (node (ref "CON_DATA_E") (pin "1") (pinfunction "1_1") (pintype "passive"))
      (node (ref "IC7") (pin "P$4") (pinfunction "(XCK0/AIN0)PE2_P$4") (pintype "bidirectional"))
    )
    (net (code "46") (name "/PE3") (class "Default")
      (node (ref "CON_DATA_E") (pin "2") (pinfunction "2_2") (pintype "passive"))
      (node (ref "IC7") (pin "P$5") (pinfunction "(OC3A/AIN1)PE3_P$5") (pintype "bidirectional"))
    )
    (net (code "47") (name "/PE4") (class "Default")
      (node (ref "CON_DATA_E") (pin "3") (pinfunction "3_3") (pintype "passive"))
      (node (ref "IC7") (pin "P$6") (pinfunction "(OC3B/INT4)PE4_P$6") (pintype "bidirectional"))
    )
    (net (code "48") (name "/PE5") (class "Default")
      (node (ref "CON_DATA_E") (pin "4") (pinfunction "4_4") (pintype "passive"))
      (node (ref "IC7") (pin "P$7") (pinfunction "(OC3C/INT5)PE5_P$7") (pintype "bidirectional"))
    )
    (net (code "49") (name "/PE6") (class "Default")
      (node (ref "CON_DATA_E") (pin "5") (pinfunction "5_5") (pintype "passive"))
      (node (ref "IC7") (pin "P$8") (pinfunction "(T3/INT6)PE6_P$8") (pintype "bidirectional"))
    )
    (net (code "50") (name "/PE7") (class "Default")
      (node (ref "CON_DATA_E") (pin "6") (pinfunction "6_6") (pintype "passive"))
      (node (ref "IC7") (pin "P$9") (pinfunction "(IC3/INT7)PE7_P$9") (pintype "bidirectional"))
    )
    (net (code "51") (name "/PWM_1") (class "Default")
      (node (ref "IC7") (pin "P$15") (pinfunction "(OC1A)PB5_P$15") (pintype "bidirectional"))
      (node (ref "JP_MOTOR1") (pin "1") (pinfunction "1_1") (pintype "passive"))
    )
    (net (code "52") (name "/PWM_2") (class "Default")
      (node (ref "IC7") (pin "P$16") (pinfunction "(OC1B)PB6_P$16") (pintype "bidirectional"))
      (node (ref "JP_MOTOR2") (pin "1") (pinfunction "1_1") (pintype "passive"))
    )
    (net (code "53") (name "/PWM_3") (class "Default")
      (node (ref "IC7") (pin "P$17") (pinfunction "(OC2/OC1C)PB7_P$17") (pintype "bidirectional"))
      (node (ref "JP_MOTOR3") (pin "1") (pinfunction "1_1") (pintype "passive"))
    )
    (net (code "54") (name "/RESET") (class "Default")
      (node (ref "IC7") (pin "P$20") (pinfunction "RESET_P$20") (pintype "input"))
      (node (ref "JP_RESET") (pin "4") (pinfunction "4_4") (pintype "passive"))
      (node (ref "SV1") (pin "5") (pinfunction "5_5") (pintype "passive"))
      (node (ref "T2") (pin "1") (pinfunction "C_1") (pintype "passive"))
    )
    (net (code "55") (name "/RX0") (class "Default")
      (node (ref "IC7") (pin "P$2") (pinfunction "(RXD/PDI)PE0_P$2") (pintype "bidirectional"))
      (node (ref "R_RX") (pin "2") (pinfunction "2_2") (pintype "passive"))
    )
    (net (code "56") (name "/RX1") (class "Default")
      (node (ref "IC7") (pin "P$27") (pinfunction "(RXD1/INT2)PD2_P$27") (pintype "bidirectional"))
      (node (ref "X1") (pin "3") (pinfunction "S_3") (pintype "passive"))
    )
    (net (code "57") (name "/SCK") (class "Default")
      (node (ref "IC7") (pin "P$11") (pinfunction "(SCK)PB1_P$11") (pintype "bidirectional"))
      (node (ref "SV1") (pin "7") (pinfunction "7_7") (pintype "passive"))
    )
    (net (code "58") (name "/SCL") (class "Default")
      (node (ref "IC7") (pin "P$25") (pinfunction "(SCL/INT0)PD0_P$25") (pintype "bidirectional"))
      (node (ref "R_U2") (pin "1") (pinfunction "1_1") (pintype "passive"))
      (node (ref "X2") (pin "5") (pinfunction "S_5") (pintype "passive"))
      (node (ref "X2") (pin "6") (pinfunction "S_6") (pintype "passive"))
    )
    (net (code "59") (name "/SDA") (class "Default")
      (node (ref "IC7") (pin "P$26") (pinfunction "(SDA/INT1)PD1_P$26") (pintype "bidirectional"))
      (node (ref "R_U1") (pin "1") (pinfunction "1_1") (pintype "passive"))
      (node (ref "X2") (pin "3") (pinfunction "S_3") (pintype "passive"))
      (node (ref "X2") (pin "4") (pinfunction "S_4") (pintype "passive"))
    )
    (net (code "60") (name "/SERVO1") (class "Default")
      (node (ref "IC7") (pin "P$29") (pinfunction "(IC1)PD4_P$29") (pintype "bidirectional"))
      (node (ref "JP_SERVO1") (pin "2") (pinfunction "2_2") (pintype "passive"))
    )
    (net (code "61") (name "/SERVO2") (class "Default")
      (node (ref "IC7") (pin "P$30") (pinfunction "(XCK1)PD5_P$30") (pintype "bidirectional"))
      (node (ref "JP_SERVO1") (pin "1") (pinfunction "1_1") (pintype "passive"))
    )
    (net (code "62") (name "/SERVO3") (class "Default")
      (node (ref "IC7") (pin "P$31") (pinfunction "(T1)PD6_P$31") (pintype "bidirectional"))
      (node (ref "JP_SERVO2") (pin "2") (pinfunction "2_2") (pintype "passive"))
    )
    (net (code "63") (name "/SERVO4") (class "Default")
      (node (ref "IC7") (pin "P$32") (pinfunction "(T2)PD7_P$32") (pintype "bidirectional"))
      (node (ref "JP_SERVO2") (pin "1") (pinfunction "1_1") (pintype "passive"))
    )
    (net (code "64") (name "/TX0") (class "Default")
      (node (ref "IC2") (pin "11") (pinfunction "T1IN_11") (pintype "input"))
      (node (ref "IC7") (pin "P$3") (pinfunction "(TXD/PDO)PE1_P$3") (pintype "bidirectional"))
    )
    (net (code "65") (name "/TX1") (class "Default")
      (node (ref "IC7") (pin "P$28") (pinfunction "(TXD1/INT3)PD3_P$28") (pintype "bidirectional"))
      (node (ref "X1") (pin "2") (pinfunction "S_2") (pintype "passive"))
    )
    (net (code "66") (name "GND") (class "Default")
      (node (ref "CON_VCC_A") (pin "10") (pinfunction "10_10") (pintype "passive"))
      (node (ref "CON_VCC_A") (pin "12") (pinfunction "12_12") (pintype "passive"))
      (node (ref "CON_VCC_A") (pin "14") (pinfunction "14_14") (pintype "passive"))
      (node (ref "CON_VCC_A") (pin "16") (pinfunction "16_16") (pintype "passive"))
      (node (ref "CON_VCC_A") (pin "2") (pinfunction "2_2") (pintype "passive"))
      (node (ref "CON_VCC_A") (pin "4") (pinfunction "4_4") (pintype "passive"))
      (node (ref "CON_VCC_A") (pin "6") (pinfunction "6_6") (pintype "passive"))
      (node (ref "CON_VCC_A") (pin "8") (pinfunction "8_8") (pintype "passive"))
      (node (ref "CON_VCC_C") (pin "10") (pinfunction "10_10") (pintype "passive"))
      (node (ref "CON_VCC_C") (pin "12") (pinfunction "12_12") (pintype "passive"))
      (node (ref "CON_VCC_C") (pin "14") (pinfunction "14_14") (pintype "passive"))
      (node (ref "CON_VCC_C") (pin "16") (pinfunction "16_16") (pintype "passive"))
      (node (ref "CON_VCC_C") (pin "2") (pinfunction "2_2") (pintype "passive"))
      (node (ref "CON_VCC_C") (pin "4") (pinfunction "4_4") (pintype "passive"))
      (node (ref "CON_VCC_C") (pin "6") (pinfunction "6_6") (pintype "passive"))
      (node (ref "CON_VCC_C") (pin "8") (pinfunction "8_8") (pintype "passive"))
      (node (ref "CON_VCC_E") (pin "10") (pinfunction "10_10") (pintype "passive"))
      (node (ref "CON_VCC_E") (pin "12") (pinfunction "12_12") (pintype "passive"))
      (node (ref "CON_VCC_E") (pin "2") (pinfunction "2_2") (pintype "passive"))
      (node (ref "CON_VCC_E") (pin "4") (pinfunction "4_4") (pintype "passive"))
      (node (ref "CON_VCC_E") (pin "6") (pinfunction "6_6") (pintype "passive"))
      (node (ref "CON_VCC_E") (pin "8") (pinfunction "8_8") (pintype "passive"))
      (node (ref "C_AR") (pin "1") (pinfunction "1_1") (pintype "passive"))
      (node (ref "C_F1") (pin "2") (pinfunction "2_2") (pintype "passive"))
      (node (ref "C_F10") (pin "2") (pinfunction "2_2") (pintype "passive"))
      (node (ref "C_F11") (pin "1") (pinfunction "1_1") (pintype "passive"))
      (node (ref "C_F12") (pin "2") (pinfunction "2_2") (pintype "passive"))
      (node (ref "C_F13") (pin "2") (pinfunction "2_2") (pintype "passive"))
      (node (ref "C_F14") (pin "2") (pinfunction "2_2") (pintype "passive"))
      (node (ref "C_F2") (pin "2") (pinfunction "2_2") (pintype "passive"))
      (node (ref "C_F3") (pin "2") (pinfunction "2_2") (pintype "passive"))
      (node (ref "C_F4") (pin "2") (pinfunction "2_2") (pintype "passive"))
      (node (ref "C_F5") (pin "2") (pinfunction "2_2") (pintype "passive"))
      (node (ref "C_F6") (pin "2") (pinfunction "2_2") (pintype "passive"))
      (node (ref "C_F7") (pin "2") (pinfunction "2_2") (pintype "passive"))
      (node (ref "C_F8") (pin "2") (pinfunction "2_2") (pintype "passive"))
      (node (ref "C_F9") (pin "2") (pinfunction "2_2") (pintype "passive"))
      (node (ref "C_FA") (pin "2") (pinfunction "2_2") (pintype "passive"))
      (node (ref "C_FC") (pin "2") (pinfunction "2_2") (pintype "passive"))
      (node (ref "C_FE") (pin "2") (pinfunction "2_2") (pintype "passive"))
      (node (ref "C_FS") (pin "2") (pinfunction "2_2") (pintype "passive"))
      (node (ref "C_M1") (pin "2") (pinfunction "2_2") (pintype "passive"))
      (node (ref "C_M2") (pin "2") (pinfunction "2_2") (pintype "passive"))
      (node (ref "C_M3") (pin "2") (pinfunction "2_2") (pintype "passive"))
      (node (ref "C_Q1") (pin "1") (pinfunction "1_1") (pintype "passive"))
      (node (ref "C_Q2") (pin "1") (pinfunction "1_1") (pintype "passive"))
      (node (ref "C_V1") (pin "-") (pinfunction "-_-") (pintype "passive"))
      (node (ref "C_V2") (pin "2") (pinfunction "2_2") (pintype "passive"))
      (node (ref "C_V3") (pin "2") (pinfunction "2_2") (pintype "passive"))
      (node (ref "C_V4") (pin "2") (pinfunction "2_2") (pintype "passive"))
      (node (ref "C_X3") (pin "+") (pinfunction "+_+") (pintype "passive"))
      (node (ref "D11") (pin "A") (pinfunction "A_A") (pintype "passive"))
      (node (ref "D12") (pin "A") (pinfunction "A_A") (pintype "passive"))
      (node (ref "D3") (pin "A") (pinfunction "A_A") (pintype "passive"))
      (node (ref "D4") (pin "A") (pinfunction "A_A") (pintype "passive"))
      (node (ref "D7") (pin "A") (pinfunction "A_A") (pintype "passive"))
      (node (ref "D8") (pin "A") (pinfunction "A_A") (pintype "passive"))
      (node (ref "D_T1") (pin "A") (pinfunction "A_A") (pintype "passive"))
      (node (ref "D_T2") (pin "A") (pinfunction "A_A") (pintype "passive"))
      (node (ref "IC1") (pin "GND") (pinfunction "GND_GND") (pintype "input"))
      (node (ref "IC2") (pin "15") (pinfunction "GND_15") (pintype "power_in"))
      (node (ref "IC3") (pin "1") (pinfunction "SEN_A_1") (pintype "input"))
      (node (ref "IC3") (pin "15") (pinfunction "SEN_B_15") (pintype "input"))
      (node (ref "IC3") (pin "8") (pinfunction "GND_8") (pintype "power_in"))
      (node (ref "IC4") (pin "1") (pinfunction "SEN_A_1") (pintype "input"))
      (node (ref "IC4") (pin "15") (pinfunction "SEN_B_15") (pintype "input"))
      (node (ref "IC4") (pin "8") (pinfunction "GND_8") (pintype "power_in"))
      (node (ref "IC5") (pin "1") (pinfunction "SEN_A_1") (pintype "input"))
      (node (ref "IC5") (pin "15") (pinfunction "SEN_B_15") (pintype "input"))
      (node (ref "IC5") (pin "8") (pinfunction "GND_8") (pintype "power_in"))
      (node (ref "IC6") (pin "7") (pinfunction "GND_7") (pintype "power_in"))
      (node (ref "IC7") (pin "P$22") (pinfunction "GND_P$22") (pintype "power_in"))
      (node (ref "IC7") (pin "P$53") (pinfunction "GND_P$53") (pintype "power_in"))
      (node (ref "IC7") (pin "P$63") (pinfunction "GND_P$63") (pintype "power_in"))
      (node (ref "IC8") (pin "GND") (pinfunction "GND_GND") (pintype "input"))
      (node (ref "JP6") (pin "1") (pinfunction "1_1") (pintype "passive"))
      (node (ref "JP6") (pin "16") (pinfunction "16_16") (pintype "passive"))
      (node (ref "JP_RESET") (pin "1") (pinfunction "1_1") (pintype "passive"))
      (node (ref "JP_RESET") (pin "3") (pinfunction "3_3") (pintype "passive"))
      (node (ref "JP_SERVO1") (pin "5") (pinfunction "5_5") (pintype "passive"))
      (node (ref "JP_SERVO1") (pin "6") (pinfunction "6_6") (pintype "passive"))
      (node (ref "JP_SERVO2") (pin "5") (pinfunction "5_5") (pintype "passive"))
      (node (ref "JP_SERVO2") (pin "6") (pinfunction "6_6") (pintype "passive"))
      (node (ref "LED1") (pin "K") (pinfunction "C_K") (pintype "passive"))
      (node (ref "R12") (pin "1") (pinfunction "1_1") (pintype "passive"))
      (node (ref "R5") (pin "1") (pinfunction "1_1") (pintype "passive"))
      (node (ref "R7") (pin "1") (pinfunction "1_1") (pintype "passive"))
      (node (ref "RS1") (pin "5") (pinfunction "5_5") (pintype "passive"))
      (node (ref "R_D1") (pin "1") (pinfunction "1_1") (pintype "passive"))
      (node (ref "R_D2") (pin "2") (pinfunction "2_2") (pintype "passive"))
      (node (ref "R_D3") (pin "1") (pinfunction "1_1") (pintype "passive"))
      (node (ref "R_P1") (pin "2") (pinfunction "2_2") (pintype "passive"))
      (node (ref "S1") (pin "3") (pinfunction "P_3") (pintype "passive"))
      (node (ref "S1") (pin "4") (pinfunction "P1_4") (pintype "passive"))
      (node (ref "SV1") (pin "10") (pinfunction "10_10") (pintype "passive"))
      (node (ref "SV1") (pin "4") (pinfunction "4_4") (pintype "passive"))
      (node (ref "SV1") (pin "6") (pinfunction "6_6") (pintype "passive"))
      (node (ref "SV1") (pin "8") (pinfunction "8_8") (pintype "passive"))
      (node (ref "T1") (pin "3") (pinfunction "E_3") (pintype "passive"))
      (node (ref "T2") (pin "3") (pinfunction "E_3") (pintype "passive"))
      (node (ref "T3") (pin "3") (pinfunction "E_3") (pintype "passive"))
      (node (ref "X1") (pin "4") (pinfunction "S_4") (pintype "passive"))
      (node (ref "X2") (pin "7") (pinfunction "S_7") (pintype "passive"))
      (node (ref "X2") (pin "8") (pinfunction "S_8") (pintype "passive"))
      (node (ref "X6V") (pin "2") (pinfunction "KL_2") (pintype "passive"))
    )
    (net (code "67") (name "Net-(C_L1-Pad1)") (class "Default")
      (node (ref "C_L1") (pin "1") (pinfunction "1_1") (pintype "passive"))
      (node (ref "LED2") (pin "C") (pinfunction "C_C") (pintype "passive"))
      (node (ref "LED3") (pin "A") (pinfunction "A_A") (pintype "passive"))
      (node (ref "R_L1") (pin "1") (pinfunction "1_1") (pintype "passive"))
    )
    (net (code "68") (name "Net-(C_L2-Pad1)") (class "Default")
      (node (ref "C_L2") (pin "1") (pinfunction "1_1") (pintype "passive"))
      (node (ref "LED4") (pin "C") (pinfunction "C_C") (pintype "passive"))
      (node (ref "LED5") (pin "A") (pinfunction "A_A") (pintype "passive"))
      (node (ref "R_L2") (pin "1") (pinfunction "1_1") (pintype "passive"))
    )
    (net (code "69") (name "Net-(C_L3-Pad1)") (class "Default")
      (node (ref "C_L3") (pin "1") (pinfunction "1_1") (pintype "passive"))
      (node (ref "LED6") (pin "C") (pinfunction "C_C") (pintype "passive"))
      (node (ref "LED7") (pin "A") (pinfunction "A_A") (pintype "passive"))
      (node (ref "R_L3") (pin "1") (pinfunction "1_1") (pintype "passive"))
    )
    (net (code "70") (name "Net-(IC2A-C1+)") (class "Default")
      (node (ref "C_X1") (pin "+") (pinfunction "+_+") (pintype "passive"))
      (node (ref "IC2") (pin "1") (pinfunction "C1+_1") (pintype "bidirectional"))
    )
    (net (code "71") (name "Net-(IC2A-C1-)") (class "Default")
      (node (ref "C_X1") (pin "-") (pinfunction "-_-") (pintype "passive"))
      (node (ref "IC2") (pin "3") (pinfunction "C1-_3") (pintype "bidirectional"))
    )
    (net (code "72") (name "Net-(IC2A-C2+)") (class "Default")
      (node (ref "C_X2") (pin "+") (pinfunction "+_+") (pintype "passive"))
      (node (ref "IC2") (pin "4") (pinfunction "C2+_4") (pintype "bidirectional"))
    )
    (net (code "73") (name "Net-(IC2A-C2-)") (class "Default")
      (node (ref "C_X2") (pin "-") (pinfunction "-_-") (pintype "passive"))
      (node (ref "IC2") (pin "5") (pinfunction "C2-_5") (pintype "bidirectional"))
    )
    (net (code "74") (name "Net-(IC2A-R1OUT)") (class "Default")
      (node (ref "IC2") (pin "12") (pinfunction "R1OUT_12") (pintype "output"))
      (node (ref "R_RX") (pin "1") (pinfunction "1_1") (pintype "passive"))
    )
    (net (code "75") (name "Net-(IC2A-V+)") (class "Default")
      (node (ref "C_X4") (pin "+") (pinfunction "+_+") (pintype "passive"))
      (node (ref "IC2") (pin "2") (pinfunction "V+_2") (pintype "bidirectional"))
    )
    (net (code "76") (name "Net-(IC2A-V-)") (class "Default")
      (node (ref "C_X3") (pin "-") (pinfunction "-_-") (pintype "passive"))
      (node (ref "IC2") (pin "6") (pinfunction "V-_6") (pintype "bidirectional"))
    )
    (net (code "77") (name "Net-(IC3-ENABLE_A)") (class "Default")
      (node (ref "IC3") (pin "11") (pinfunction "ENABLE_B_11") (pintype "input"))
      (node (ref "IC3") (pin "6") (pinfunction "ENABLE_A_6") (pintype "input"))
      (node (ref "JP_MOTOR1") (pin "2") (pinfunction "2_2") (pintype "passive"))
      (node (ref "R12") (pin "2") (pinfunction "2_2") (pintype "passive"))
    )
    (net (code "78") (name "Net-(IC3-INPUT1)") (class "Default")
      (node (ref "IC3") (pin "12") (pinfunction "INPUT4_12") (pintype "input"))
      (node (ref "IC3") (pin "5") (pinfunction "INPUT1_5") (pintype "input"))
      (node (ref "IC6") (pin "8") (pinfunction "O_8") (pintype "output"))
    )
    (net (code "79") (name "Net-(IC3-INPUT2)") (class "Default")
      (node (ref "IC3") (pin "10") (pinfunction "INPUT3_10") (pintype "input"))
      (node (ref "IC3") (pin "7") (pinfunction "INPUT2_7") (pintype "input"))
      (node (ref "IC6") (pin "6") (pinfunction "O_6") (pintype "output"))
      (node (ref "IC6") (pin "9") (pinfunction "I_9") (pintype "input"))
    )
    (net (code "80") (name "Net-(IC4-ENABLE_A)") (class "Default")
      (node (ref "IC4") (pin "11") (pinfunction "ENABLE_B_11") (pintype "input"))
      (node (ref "IC4") (pin "6") (pinfunction "ENABLE_A_6") (pintype "input"))
      (node (ref "JP_MOTOR2") (pin "2") (pinfunction "2_2") (pintype "passive"))
      (node (ref "R7") (pin "2") (pinfunction "2_2") (pintype "passive"))
    )
    (net (code "81") (name "Net-(IC4-INPUT1)") (class "Default")
      (node (ref "IC4") (pin "12") (pinfunction "INPUT4_12") (pintype "input"))
      (node (ref "IC4") (pin "5") (pinfunction "INPUT1_5") (pintype "input"))
      (node (ref "IC6") (pin "10") (pinfunction "O_10") (pintype "output"))
    )
    (net (code "82") (name "Net-(IC4-INPUT2)") (class "Default")
      (node (ref "IC4") (pin "10") (pinfunction "INPUT3_10") (pintype "input"))
      (node (ref "IC4") (pin "7") (pinfunction "INPUT2_7") (pintype "input"))
      (node (ref "IC6") (pin "11") (pinfunction "I_11") (pintype "input"))
      (node (ref "IC6") (pin "4") (pinfunction "O_4") (pintype "output"))
    )
    (net (code "83") (name "Net-(IC5-ENABLE_A)") (class "Default")
      (node (ref "IC5") (pin "11") (pinfunction "ENABLE_B_11") (pintype "input"))
      (node (ref "IC5") (pin "6") (pinfunction "ENABLE_A_6") (pintype "input"))
      (node (ref "JP_MOTOR3") (pin "2") (pinfunction "2_2") (pintype "passive"))
      (node (ref "R5") (pin "2") (pinfunction "2_2") (pintype "passive"))
    )
    (net (code "84") (name "Net-(IC5-INPUT1)") (class "Default")
      (node (ref "IC5") (pin "12") (pinfunction "INPUT4_12") (pintype "input"))
      (node (ref "IC5") (pin "5") (pinfunction "INPUT1_5") (pintype "input"))
      (node (ref "IC6") (pin "12") (pinfunction "O_12") (pintype "output"))
    )
    (net (code "85") (name "Net-(IC5-INPUT2)") (class "Default")
      (node (ref "IC5") (pin "10") (pinfunction "INPUT3_10") (pintype "input"))
      (node (ref "IC5") (pin "7") (pinfunction "INPUT2_7") (pintype "input"))
      (node (ref "IC6") (pin "13") (pinfunction "I_13") (pintype "input"))
      (node (ref "IC6") (pin "2") (pinfunction "O_2") (pintype "output"))
    )
    (net (code "86") (name "Net-(IC6A-I)") (class "Default")
      (node (ref "IC6") (pin "1") (pinfunction "I_1") (pintype "input"))
      (node (ref "JP_MOTOR3") (pin "4") (pinfunction "4_4") (pintype "passive"))
    )
    (net (code "87") (name "Net-(IC6B-I)") (class "Default")
      (node (ref "IC6") (pin "3") (pinfunction "I_3") (pintype "input"))
      (node (ref "JP_MOTOR2") (pin "4") (pinfunction "4_4") (pintype "passive"))
    )
    (net (code "88") (name "Net-(IC6C-I)") (class "Default")
      (node (ref "IC6") (pin "5") (pinfunction "I_5") (pintype "input"))
      (node (ref "JP_MOTOR1") (pin "4") (pinfunction "4_4") (pintype "passive"))
    )
    (net (code "89") (name "Net-(IC7-AREF)") (class "Default")
      (node (ref "C_AR") (pin "2") (pinfunction "2_2") (pintype "passive"))
      (node (ref "IC7") (pin "P$62") (pinfunction "AREF_P$62") (pintype "passive"))
    )
    (net (code "90") (name "Net-(IC7-XTAL1)") (class "Default")
      (node (ref "C_Q2") (pin "2") (pinfunction "2_2") (pintype "passive"))
      (node (ref "IC7") (pin "P$24") (pinfunction "XTAL1_P$24") (pintype "bidirectional"))
      (node (ref "Q1") (pin "1") (pinfunction "1_1") (pintype "passive"))
    )
    (net (code "91") (name "Net-(IC7-XTAL2)") (class "Default")
      (node (ref "C_Q1") (pin "2") (pinfunction "2_2") (pintype "passive"))
      (node (ref "IC7") (pin "P$23") (pinfunction "XTAL2_P$23") (pintype "bidirectional"))
      (node (ref "Q1") (pin "2") (pinfunction "2_2") (pintype "passive"))
    )
    (net (code "92") (name "Net-(JP6-Pad3)") (class "Default")
      (node (ref "JP6") (pin "3") (pinfunction "3_3") (pintype "passive"))
      (node (ref "R_P1") (pin "3") (pinfunction "3_3") (pintype "passive"))
    )
    (net (code "93") (name "Net-(JP6-Pad15)") (class "Default")
      (node (ref "JP6") (pin "15") (pinfunction "15_15") (pintype "passive"))
      (node (ref "R_LCD") (pin "2") (pinfunction "2_2") (pintype "passive"))
    )
    (net (code "94") (name "Net-(JP_TWI1-Pad2)") (class "Default")
      (node (ref "JP_TWI1") (pin "2") (pinfunction "2_2") (pintype "passive"))
      (node (ref "R_U1") (pin "2") (pinfunction "2_2") (pintype "passive"))
    )
    (net (code "95") (name "Net-(JP_TWI2-Pad2)") (class "Default")
      (node (ref "JP_TWI2") (pin "2") (pinfunction "2_2") (pintype "passive"))
      (node (ref "R_U2") (pin "2") (pinfunction "2_2") (pintype "passive"))
    )
    (net (code "96") (name "Net-(JP_UART-Pad2)") (class "Default")
      (node (ref "JP_UART") (pin "2") (pinfunction "2_2") (pintype "passive"))
      (node (ref "R_D1") (pin "2") (pinfunction "2_2") (pintype "passive"))
      (node (ref "R_T1") (pin "1") (pinfunction "1_1") (pintype "passive"))
    )
    (net (code "97") (name "Net-(JP_UART-Pad4)") (class "Default")
      (node (ref "JP_UART") (pin "4") (pinfunction "4_4") (pintype "passive"))
      (node (ref "R_D2") (pin "1") (pinfunction "1_1") (pintype "passive"))
      (node (ref "R_T2") (pin "1") (pinfunction "1_1") (pintype "passive"))
    )
    (net (code "98") (name "Net-(T1-B)") (class "Default")
      (node (ref "D_T1") (pin "C") (pinfunction "C_C") (pintype "passive"))
      (node (ref "R_T1") (pin "2") (pinfunction "2_2") (pintype "passive"))
      (node (ref "T1") (pin "2") (pinfunction "B_2") (pintype "passive"))
    )
    (net (code "99") (name "Net-(T2-B)") (class "Default")
      (node (ref "D_T2") (pin "C") (pinfunction "C_C") (pintype "passive"))
      (node (ref "R_T2") (pin "2") (pinfunction "2_2") (pintype "passive"))
      (node (ref "T2") (pin "2") (pinfunction "B_2") (pintype "passive"))
    )
    (net (code "100") (name "Net-(T3-B)") (class "Default")
      (node (ref "R_T3") (pin "2") (pinfunction "2_2") (pintype "passive"))
      (node (ref "T3") (pin "2") (pinfunction "B_2") (pintype "passive"))
    )
    (net (code "101") (name "Net-(T3-C)") (class "Default")
      (node (ref "R_S1") (pin "1") (pinfunction "1_1") (pintype "passive"))
      (node (ref "SP1") (pin "1") (pinfunction "1_1") (pintype "passive"))
      (node (ref "T3") (pin "1") (pinfunction "C_1") (pintype "passive"))
    )
    (net (code "102") (name "Net-(X6VC-KL)") (class "Default")
      (node (ref "D_V1") (pin "A") (pinfunction "A_A") (pintype "passive"))
      (node (ref "X6V") (pin "3") (pinfunction "KL_3") (pintype "passive"))
    )
    (net (code "103") (name "V+") (class "Default")
      (node (ref "C_F13") (pin "1") (pinfunction "1_1") (pintype "passive"))
      (node (ref "C_FS") (pin "1") (pinfunction "1_1") (pintype "passive"))
      (node (ref "C_V4") (pin "1") (pinfunction "1_1") (pintype "passive"))
      (node (ref "IC8") (pin "OUT") (pinfunction "OUT_OUT") (pintype "passive"))
      (node (ref "JP_SERVO1") (pin "3") (pinfunction "3_3") (pintype "passive"))
      (node (ref "JP_SERVO1") (pin "4") (pinfunction "4_4") (pintype "passive"))
      (node (ref "JP_SERVO2") (pin "3") (pinfunction "3_3") (pintype "passive"))
      (node (ref "JP_SERVO2") (pin "4") (pinfunction "4_4") (pintype "passive"))
    )
    (net (code "104") (name "V_MCU") (class "Default")
      (node (ref "C_F1") (pin "1") (pinfunction "1_1") (pintype "passive"))
      (node (ref "C_V1") (pin "+") (pinfunction "+_+") (pintype "passive"))
      (node (ref "D_V1") (pin "C") (pinfunction "C_C") (pintype "passive"))
      (node (ref "D_V2") (pin "C") (pinfunction "C_C") (pintype "passive"))
      (node (ref "IC1") (pin "IN") (pinfunction "IN_IN") (pintype "input"))
    )
    (net (code "105") (name "V_Motor") (class "Default")
      (node (ref "C_F10") (pin "1") (pinfunction "1_1") (pintype "passive"))
      (node (ref "C_F14") (pin "1") (pinfunction "1_1") (pintype "passive"))
      (node (ref "C_F6") (pin "1") (pinfunction "1_1") (pintype "passive"))
      (node (ref "C_F8") (pin "1") (pinfunction "1_1") (pintype "passive"))
      (node (ref "C_V3") (pin "1") (pinfunction "1_1") (pintype "passive"))
      (node (ref "D1") (pin "C") (pinfunction "C_C") (pintype "passive"))
      (node (ref "D10") (pin "C") (pinfunction "C_C") (pintype "passive"))
      (node (ref "D2") (pin "C") (pinfunction "C_C") (pintype "passive"))
      (node (ref "D5") (pin "C") (pinfunction "C_C") (pintype "passive"))
      (node (ref "D6") (pin "C") (pinfunction "C_C") (pintype "passive"))
      (node (ref "D9") (pin "C") (pinfunction "C_C") (pintype "passive"))
      (node (ref "D_V2") (pin "A") (pinfunction "A_A") (pintype "passive"))
      (node (ref "IC3") (pin "4") (pinfunction "VS_4") (pintype "power_in"))
      (node (ref "IC4") (pin "4") (pinfunction "VS_4") (pintype "power_in"))
      (node (ref "IC5") (pin "4") (pinfunction "VS_4") (pintype "power_in"))
      (node (ref "IC8") (pin "IN") (pinfunction "IN_IN") (pintype "input"))
      (node (ref "X6V") (pin "1") (pinfunction "KL_1") (pintype "passive"))
    )
    (net (code "106") (name "unconnected-(IC2A-R2IN-Pad8)") (class "Default")
      (node (ref "IC2") (pin "8") (pinfunction "R2IN_8") (pintype "input"))
    )
    (net (code "107") (name "unconnected-(IC2A-R2OUT-Pad9)") (class "Default")
      (node (ref "IC2") (pin "9") (pinfunction "R2OUT_9") (pintype "output"))
    )
    (net (code "108") (name "unconnected-(IC2A-T2IN-Pad10)") (class "Default")
      (node (ref "IC2") (pin "10") (pinfunction "T2IN_10") (pintype "input"))
    )
    (net (code "109") (name "unconnected-(IC2A-T2OUT-Pad7)") (class "Default")
      (node (ref "IC2") (pin "7") (pinfunction "T2OUT_7") (pintype "output"))
    )
    (net (code "110") (name "unconnected-(IC7-PEN-PadP$1)") (class "Default")
      (node (ref "IC7") (pin "P$1") (pinfunction "PEN_P$1") (pintype "input"))
    )
    (net (code "111") (name "unconnected-(JP6-Pad7)") (class "Default")
      (node (ref "JP6") (pin "7") (pinfunction "7_7") (pintype "passive"))
    )
    (net (code "112") (name "unconnected-(JP6-Pad8)") (class "Default")
      (node (ref "JP6") (pin "8") (pinfunction "8_8") (pintype "passive"))
    )
    (net (code "113") (name "unconnected-(JP6-Pad9)") (class "Default")
      (node (ref "JP6") (pin "9") (pinfunction "9_9") (pintype "passive"))
    )
    (net (code "114") (name "unconnected-(JP6-Pad10)") (class "Default")
      (node (ref "JP6") (pin "10") (pinfunction "10_10") (pintype "passive"))
    )
    (net (code "115") (name "unconnected-(RS1-Pad1)") (class "Default")
      (node (ref "RS1") (pin "1") (pinfunction "1_1") (pintype "passive"))
    )
    (net (code "116") (name "unconnected-(RS1-Pad6)") (class "Default")
      (node (ref "RS1") (pin "6") (pinfunction "6_6") (pintype "passive"))
    )
    (net (code "117") (name "unconnected-(RS1-Pad8)") (class "Default")
      (node (ref "RS1") (pin "8") (pinfunction "8_8") (pintype "passive"))
    )
    (net (code "118") (name "unconnected-(RS1-Pad9)") (class "Default")
      (node (ref "RS1") (pin "9") (pinfunction "9_9") (pintype "passive"))
    )
    (net (code "119") (name "unconnected-(S1-S-Pad1)") (class "Default")
      (node (ref "S1") (pin "1") (pinfunction "S_1") (pintype "passive"))
    )
    (net (code "120") (name "unconnected-(SV1-Pad3)") (class "Default")
      (node (ref "SV1") (pin "3") (pinfunction "3_3") (pintype "passive"))
    )
  )
)
